# PushUpCounterV1-1.net
KiCad netlist of a schematic drawn in EAGLE
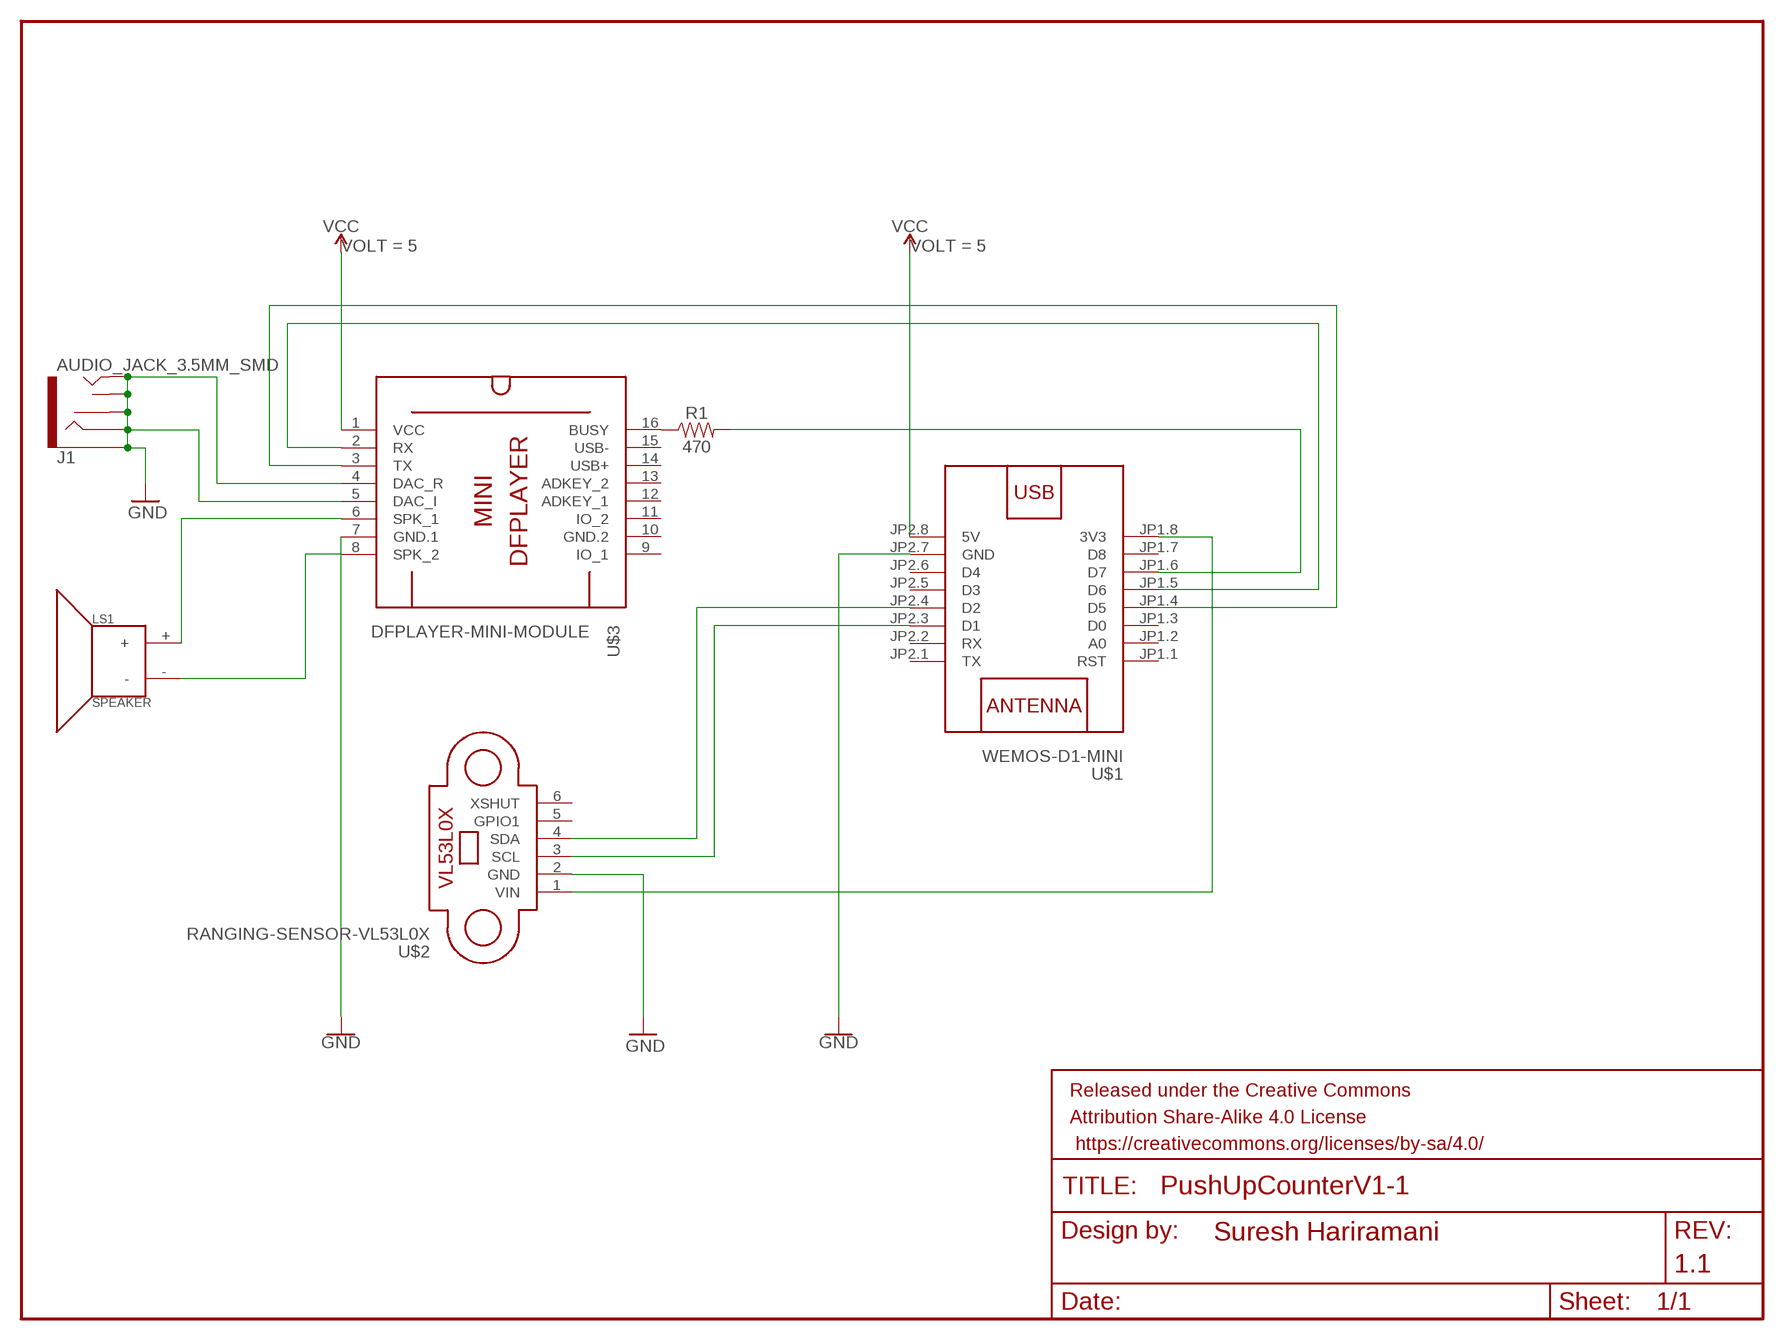
[diagram p0: schematic, sheet 1]

(export (version "E")
  (design (tool "Eeschema 10.0.6"))
  (components
    (comp (ref "FRAME1")
      (value "FRAME-LETTER")
      (footprint "eagle-import:CREATIVE_COMMONS")
      (fields (field (name "DESIGNER") "Suresh Hariramani") (field (name "REV") "1.1"))
      (libsource (lib "eagle-import") (part "FRAME-LETTER"))
    )
    (comp (ref "J1")
      (value "AUDIO_JACK_3.5MM_SMD")
      (footprint "eagle-import:AUDIO-JACK-3.5MM-SMD")
      (libsource (lib "eagle-import") (part "AUDIO_JACK_3.5MM_SMD"))
    )
    (comp (ref "LS1")
      (value "SPEAKER")
      (footprint "eagle-import:PCB_MOUNT_SPEAKER")
      (libsource (lib "eagle-import") (part "SPEAKER"))
    )
    (comp (ref "R1")
      (value "470")
      (footprint "eagle-import:0603")
      (libsource (lib "eagle-import") (part "470OHM-0603-1/10W-1%"))
    )
    (comp (ref "U$1")
      (value "WEMOS-D1-MINI")
      (footprint "eagle-import:WEMOS-D1-MINI")
      (libsource (lib "eagle-import") (part "WEMOS-D1-MINI"))
    )
    (comp (ref "U$2")
      (value "RANGING-SENSOR-VL53L0X")
      (footprint "eagle-import:RANGING-SENSOR-VL53L0X")
      (libsource (lib "eagle-import") (part "RANGING-SENSOR-VL53L0X"))
    )
    (comp (ref "U$3")
      (value "DFPLAYER-MINI-MODULE")
      (footprint "eagle-import:DFPLAYER-MINI-MODULE")
      (libsource (lib "eagle-import") (part "DFPLAYER-MINI-MODULE"))
    )
  )
  (nets
    (net (code "1") (name "/GND.2") (class "Default")
      (node (ref "U$3") (pin "10") (pinfunction "GND.2_10") (pintype "power_in"))
    )
    (net (code "2") (name "GND") (class "Default")
      (node (ref "J1") (pin "RING") (pinfunction "RING_RING") (pintype "bidirectional"))
      (node (ref "J1") (pin "RSH") (pinfunction "RSH_RSH") (pintype "bidirectional"))
      (node (ref "J1") (pin "SLEEVE") (pinfunction "SLEEVE_SLEEVE") (pintype "bidirectional"))
      (node (ref "J1") (pin "TIP") (pinfunction "TIP_TIP") (pintype "bidirectional"))
      (node (ref "J1") (pin "TSH") (pinfunction "TSH_TSH") (pintype "bidirectional"))
      (node (ref "U$1") (pin "JP2.7") (pinfunction "GND_JP2.7") (pintype "power_in"))
      (node (ref "U$2") (pin "2") (pinfunction "GND_2") (pintype "power_in"))
      (node (ref "U$3") (pin "4") (pinfunction "DAC_R_4") (pintype "bidirectional"))
      (node (ref "U$3") (pin "5") (pinfunction "DAC_I_5") (pintype "bidirectional"))
      (node (ref "U$3") (pin "7") (pinfunction "GND.1_7") (pintype "power_in"))
    )
    (net (code "3") (name "Net-(U$1-3V3)") (class "Default")
      (node (ref "U$1") (pin "JP1.8") (pinfunction "3V3_JP1.8") (pintype "power_in"))
      (node (ref "U$2") (pin "1") (pinfunction "VIN_1") (pintype "power_in"))
    )
    (net (code "4") (name "Net-(U$1-D1)") (class "Default")
      (node (ref "U$1") (pin "JP2.3") (pinfunction "D1_JP2.3") (pintype "bidirectional"))
      (node (ref "U$2") (pin "3") (pinfunction "SCL_3") (pintype "bidirectional"))
    )
    (net (code "5") (name "Net-(U$1-D2)") (class "Default")
      (node (ref "U$1") (pin "JP2.4") (pinfunction "D2_JP2.4") (pintype "bidirectional"))
      (node (ref "U$2") (pin "4") (pinfunction "SDA_4") (pintype "bidirectional"))
    )
    (net (code "6") (name "Net-(U$1-D5)") (class "Default")
      (node (ref "U$1") (pin "JP1.4") (pinfunction "D5_JP1.4") (pintype "bidirectional"))
      (node (ref "U$3") (pin "3") (pinfunction "TX_3") (pintype "bidirectional"))
    )
    (net (code "7") (name "Net-(U$1-D6)") (class "Default")
      (node (ref "U$1") (pin "JP1.5") (pinfunction "D6_JP1.5") (pintype "bidirectional"))
      (node (ref "U$3") (pin "2") (pinfunction "RX_2") (pintype "bidirectional"))
    )
    (net (code "8") (name "Net-(U$1-D7)") (class "Default")
      (node (ref "R1") (pin "2") (pinfunction "2_2") (pintype "passive"))
      (node (ref "U$1") (pin "JP1.6") (pinfunction "D7_JP1.6") (pintype "bidirectional"))
    )
    (net (code "9") (name "Net-(U$3-BUSY)") (class "Default")
      (node (ref "R1") (pin "1") (pinfunction "1_1") (pintype "passive"))
      (node (ref "U$3") (pin "16") (pinfunction "BUSY_16") (pintype "bidirectional"))
    )
    (net (code "10") (name "Net-(U$3-SPK_1)") (class "Default")
      (node (ref "LS1") (pin "+") (pinfunction "+_+") (pintype "bidirectional"))
      (node (ref "U$3") (pin "6") (pinfunction "SPK_1_6") (pintype "bidirectional"))
    )
    (net (code "11") (name "Net-(U$3-SPK_2)") (class "Default")
      (node (ref "LS1") (pin "-") (pinfunction "-_-") (pintype "bidirectional"))
      (node (ref "U$3") (pin "8") (pinfunction "SPK_2_8") (pintype "bidirectional"))
    )
    (net (code "12") (name "VCC") (class "Default")
      (node (ref "U$1") (pin "JP2.8") (pinfunction "5V_JP2.8") (pintype "power_in"))
      (node (ref "U$3") (pin "1") (pinfunction "VCC_1") (pintype "power_in"))
    )
    (net (code "13") (name "unconnected-(U$1-A0-PadJP1.2)") (class "Default")
      (node (ref "U$1") (pin "JP1.2") (pinfunction "A0_JP1.2") (pintype "bidirectional"))
    )
    (net (code "14") (name "unconnected-(U$1-D0-PadJP1.3)") (class "Default")
      (node (ref "U$1") (pin "JP1.3") (pinfunction "D0_JP1.3") (pintype "bidirectional"))
    )
    (net (code "15") (name "unconnected-(U$1-D3-PadJP2.5)") (class "Default")
      (node (ref "U$1") (pin "JP2.5") (pinfunction "D3_JP2.5") (pintype "bidirectional"))
    )
    (net (code "16") (name "unconnected-(U$1-D4-PadJP2.6)") (class "Default")
      (node (ref "U$1") (pin "JP2.6") (pinfunction "D4_JP2.6") (pintype "bidirectional"))
    )
    (net (code "17") (name "unconnected-(U$1-D8-PadJP1.7)") (class "Default")
      (node (ref "U$1") (pin "JP1.7") (pinfunction "D8_JP1.7") (pintype "bidirectional"))
    )
    (net (code "18") (name "unconnected-(U$1-RST-PadJP1.1)") (class "Default")
      (node (ref "U$1") (pin "JP1.1") (pinfunction "RST_JP1.1") (pintype "bidirectional"))
    )
    (net (code "19") (name "unconnected-(U$1-RX-PadJP2.2)") (class "Default")
      (node (ref "U$1") (pin "JP2.2") (pinfunction "RX_JP2.2") (pintype "bidirectional"))
    )
    (net (code "20") (name "unconnected-(U$1-TX-PadJP2.1)") (class "Default")
      (node (ref "U$1") (pin "JP2.1") (pinfunction "TX_JP2.1") (pintype "bidirectional"))
    )
    (net (code "21") (name "unconnected-(U$2-GPIO1-Pad5)") (class "Default")
      (node (ref "U$2") (pin "5") (pinfunction "GPIO1_5") (pintype "bidirectional"))
    )
    (net (code "22") (name "unconnected-(U$2-XSHUT-Pad6)") (class "Default")
      (node (ref "U$2") (pin "6") (pinfunction "XSHUT_6") (pintype "bidirectional"))
    )
    (net (code "23") (name "unconnected-(U$3-ADKEY_1-Pad12)") (class "Default")
      (node (ref "U$3") (pin "12") (pinfunction "ADKEY_1_12") (pintype "bidirectional"))
    )
    (net (code "24") (name "unconnected-(U$3-ADKEY_2-Pad13)") (class "Default")
      (node (ref "U$3") (pin "13") (pinfunction "ADKEY_2_13") (pintype "bidirectional"))
    )
    (net (code "25") (name "unconnected-(U$3-IO_1-Pad9)") (class "Default")
      (node (ref "U$3") (pin "9") (pinfunction "IO_1_9") (pintype "bidirectional"))
    )
    (net (code "26") (name "unconnected-(U$3-IO_2-Pad11)") (class "Default")
      (node (ref "U$3") (pin "11") (pinfunction "IO_2_11") (pintype "bidirectional"))
    )
    (net (code "27") (name "unconnected-(U$3-USB+-Pad14)") (class "Default")
      (node (ref "U$3") (pin "14") (pinfunction "USB+_14") (pintype "bidirectional"))
    )
    (net (code "28") (name "unconnected-(U$3-USB--Pad15)") (class "Default")
      (node (ref "U$3") (pin "15") (pinfunction "USB-_15") (pintype "bidirectional"))
    )
  )
)
